# NUCLEO-F410RB-Input.net
KiCad netlist of a schematic drawn in Altium Designer
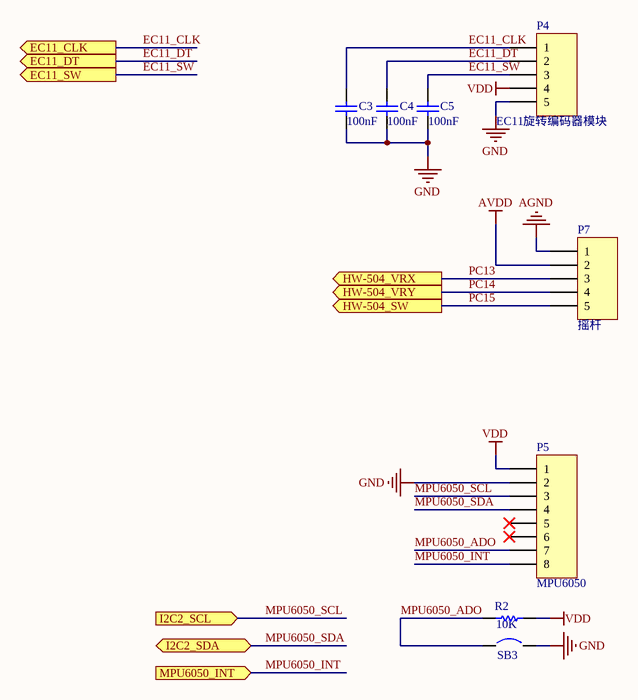
[diagram p0: NUCLEO-F410RB-Input.SchDoc]

(export (version "E")
  (design (tool "Eeschema 10.0.6"))
  (components
    (comp (ref "C3")
      (value "100nF")
      (footprint "C0603")
      (description "无极性电容")
      (fields (field (name "Comment") "Cap") (field (name "PUBLISHER") "Altium Limited"))
      (libsource (lib "Capacitor") (part "Cap"))
    )
    (comp (ref "C4")
      (value "100nF")
      (footprint "C0603")
      (description "无极性电容")
      (fields (field (name "Comment") "Cap") (field (name "PUBLISHER") "Altium Limited"))
      (libsource (lib "Capacitor") (part "Cap"))
    )
    (comp (ref "C5")
      (value "100nF")
      (footprint "C0603")
      (description "无极性电容")
      (fields (field (name "Comment") "Cap") (field (name "PUBLISHER") "Altium Limited"))
      (libsource (lib "Capacitor") (part "Cap"))
    )
    (comp (ref "P4")
      (value "EC11旋转编码器模块")
      (footprint "HDR1X5-Male")
      (description "Header, 5-Pin")
      (fields (field (name "PUBLISHER") "Altium Limited"))
      (libsource (lib "Connectors") (part "Header 5"))
    )
    (comp (ref "P5")
      (value "MPU6050")
      (footprint "HDR1X8")
      (description "Header, 8-Pin")
      (fields (field (name "PUBLISHER") "Altium Limited"))
      (libsource (lib "Connectors") (part "Header 8"))
    )
    (comp (ref "P7")
      (value "摇杆")
      (footprint "HDR1X5-Male")
      (description "Header, 5-Pin")
      (fields (field (name "PUBLISHER") "Altium Limited"))
      (libsource (lib "Connectors") (part "Header 5"))
    )
    (comp (ref "R2")
      (value "10K")
      (footprint "R0603")
      (description "Resistor")
      (fields (field (name "Comment") "Res_US") (field (name "PUBLISHER") "Altium Limited"))
      (libsource (lib "baselib") (part "Res_US"))
    )
    (comp (ref "SB3")
      (value "Circuit Breaker")
      (footprint "JP2_SMD")
      (fields (field (name "PUBLISHER") "Altium Limited"))
      (libsource (lib "baselib") (part "Circuit Breaker"))
    )
  )
  (nets
    (net (code "1") (name "/EC11_CLK") (class "Default")
      (node (ref "C3") (pin "2") (pinfunction "2_2") (pintype "passive"))
      (node (ref "P4") (pin "1") (pinfunction "1_1") (pintype "passive"))
    )
    (net (code "2") (name "/EC11_DT") (class "Default")
      (node (ref "C4") (pin "2") (pinfunction "2_2") (pintype "passive"))
      (node (ref "P4") (pin "2") (pinfunction "2_2") (pintype "passive"))
    )
    (net (code "3") (name "/EC11_SW") (class "Default")
      (node (ref "C5") (pin "2") (pinfunction "2_2") (pintype "passive"))
      (node (ref "P4") (pin "3") (pinfunction "3_3") (pintype "passive"))
    )
    (net (code "4") (name "/MPU6050_ADO") (class "Default")
      (node (ref "P5") (pin "7") (pinfunction "7_7") (pintype "passive"))
      (node (ref "R2") (pin "1") (pinfunction "1_1") (pintype "passive"))
      (node (ref "SB3") (pin "1") (pinfunction "1_1") (pintype "passive"))
    )
    (net (code "5") (name "/MPU6050_INT") (class "Default")
      (node (ref "P5") (pin "8") (pinfunction "8_8") (pintype "passive"))
    )
    (net (code "6") (name "/MPU6050_SCL") (class "Default")
      (node (ref "P5") (pin "3") (pinfunction "3_3") (pintype "passive"))
    )
    (net (code "7") (name "/MPU6050_SDA") (class "Default")
      (node (ref "P5") (pin "4") (pinfunction "4_4") (pintype "passive"))
    )
    (net (code "8") (name "/PC13") (class "Default")
      (node (ref "P7") (pin "3") (pinfunction "3_3") (pintype "passive"))
    )
    (net (code "9") (name "/PC14") (class "Default")
      (node (ref "P7") (pin "4") (pinfunction "4_4") (pintype "passive"))
    )
    (net (code "10") (name "/PC15") (class "Default")
      (node (ref "P7") (pin "5") (pinfunction "5_5") (pintype "passive"))
    )
    (net (code "11") (name "AGND") (class "Default")
      (node (ref "P7") (pin "1") (pinfunction "1_1") (pintype "passive"))
    )
    (net (code "12") (name "AVDD") (class "Default")
      (node (ref "P7") (pin "2") (pinfunction "2_2") (pintype "passive"))
    )
    (net (code "13") (name "GND") (class "Default")
      (node (ref "C3") (pin "1") (pinfunction "1_1") (pintype "passive"))
      (node (ref "C4") (pin "1") (pinfunction "1_1") (pintype "passive"))
      (node (ref "C5") (pin "1") (pinfunction "1_1") (pintype "passive"))
      (node (ref "P4") (pin "5") (pinfunction "5_5") (pintype "passive"))
      (node (ref "P5") (pin "2") (pinfunction "2_2") (pintype "passive"))
      (node (ref "SB3") (pin "2") (pinfunction "2_2") (pintype "passive"))
    )
    (net (code "14") (name "VDD") (class "Default")
      (node (ref "P4") (pin "4") (pinfunction "4_4") (pintype "passive"))
      (node (ref "P5") (pin "1") (pinfunction "1_1") (pintype "passive"))
      (node (ref "R2") (pin "2") (pinfunction "2_2") (pintype "passive"))
    )
    (net (code "15") (name "unconnected-(P5-Pad5)") (class "Default")
      (node (ref "P5") (pin "5") (pinfunction "5_5") (pintype "passive+no_connect"))
    )
    (net (code "16") (name "unconnected-(P5-Pad6)") (class "Default")
      (node (ref "P5") (pin "6") (pinfunction "6_6") (pintype "passive+no_connect"))
    )
  )
)
